# uC.net
KiCad netlist of a schematic drawn in Altium Designer
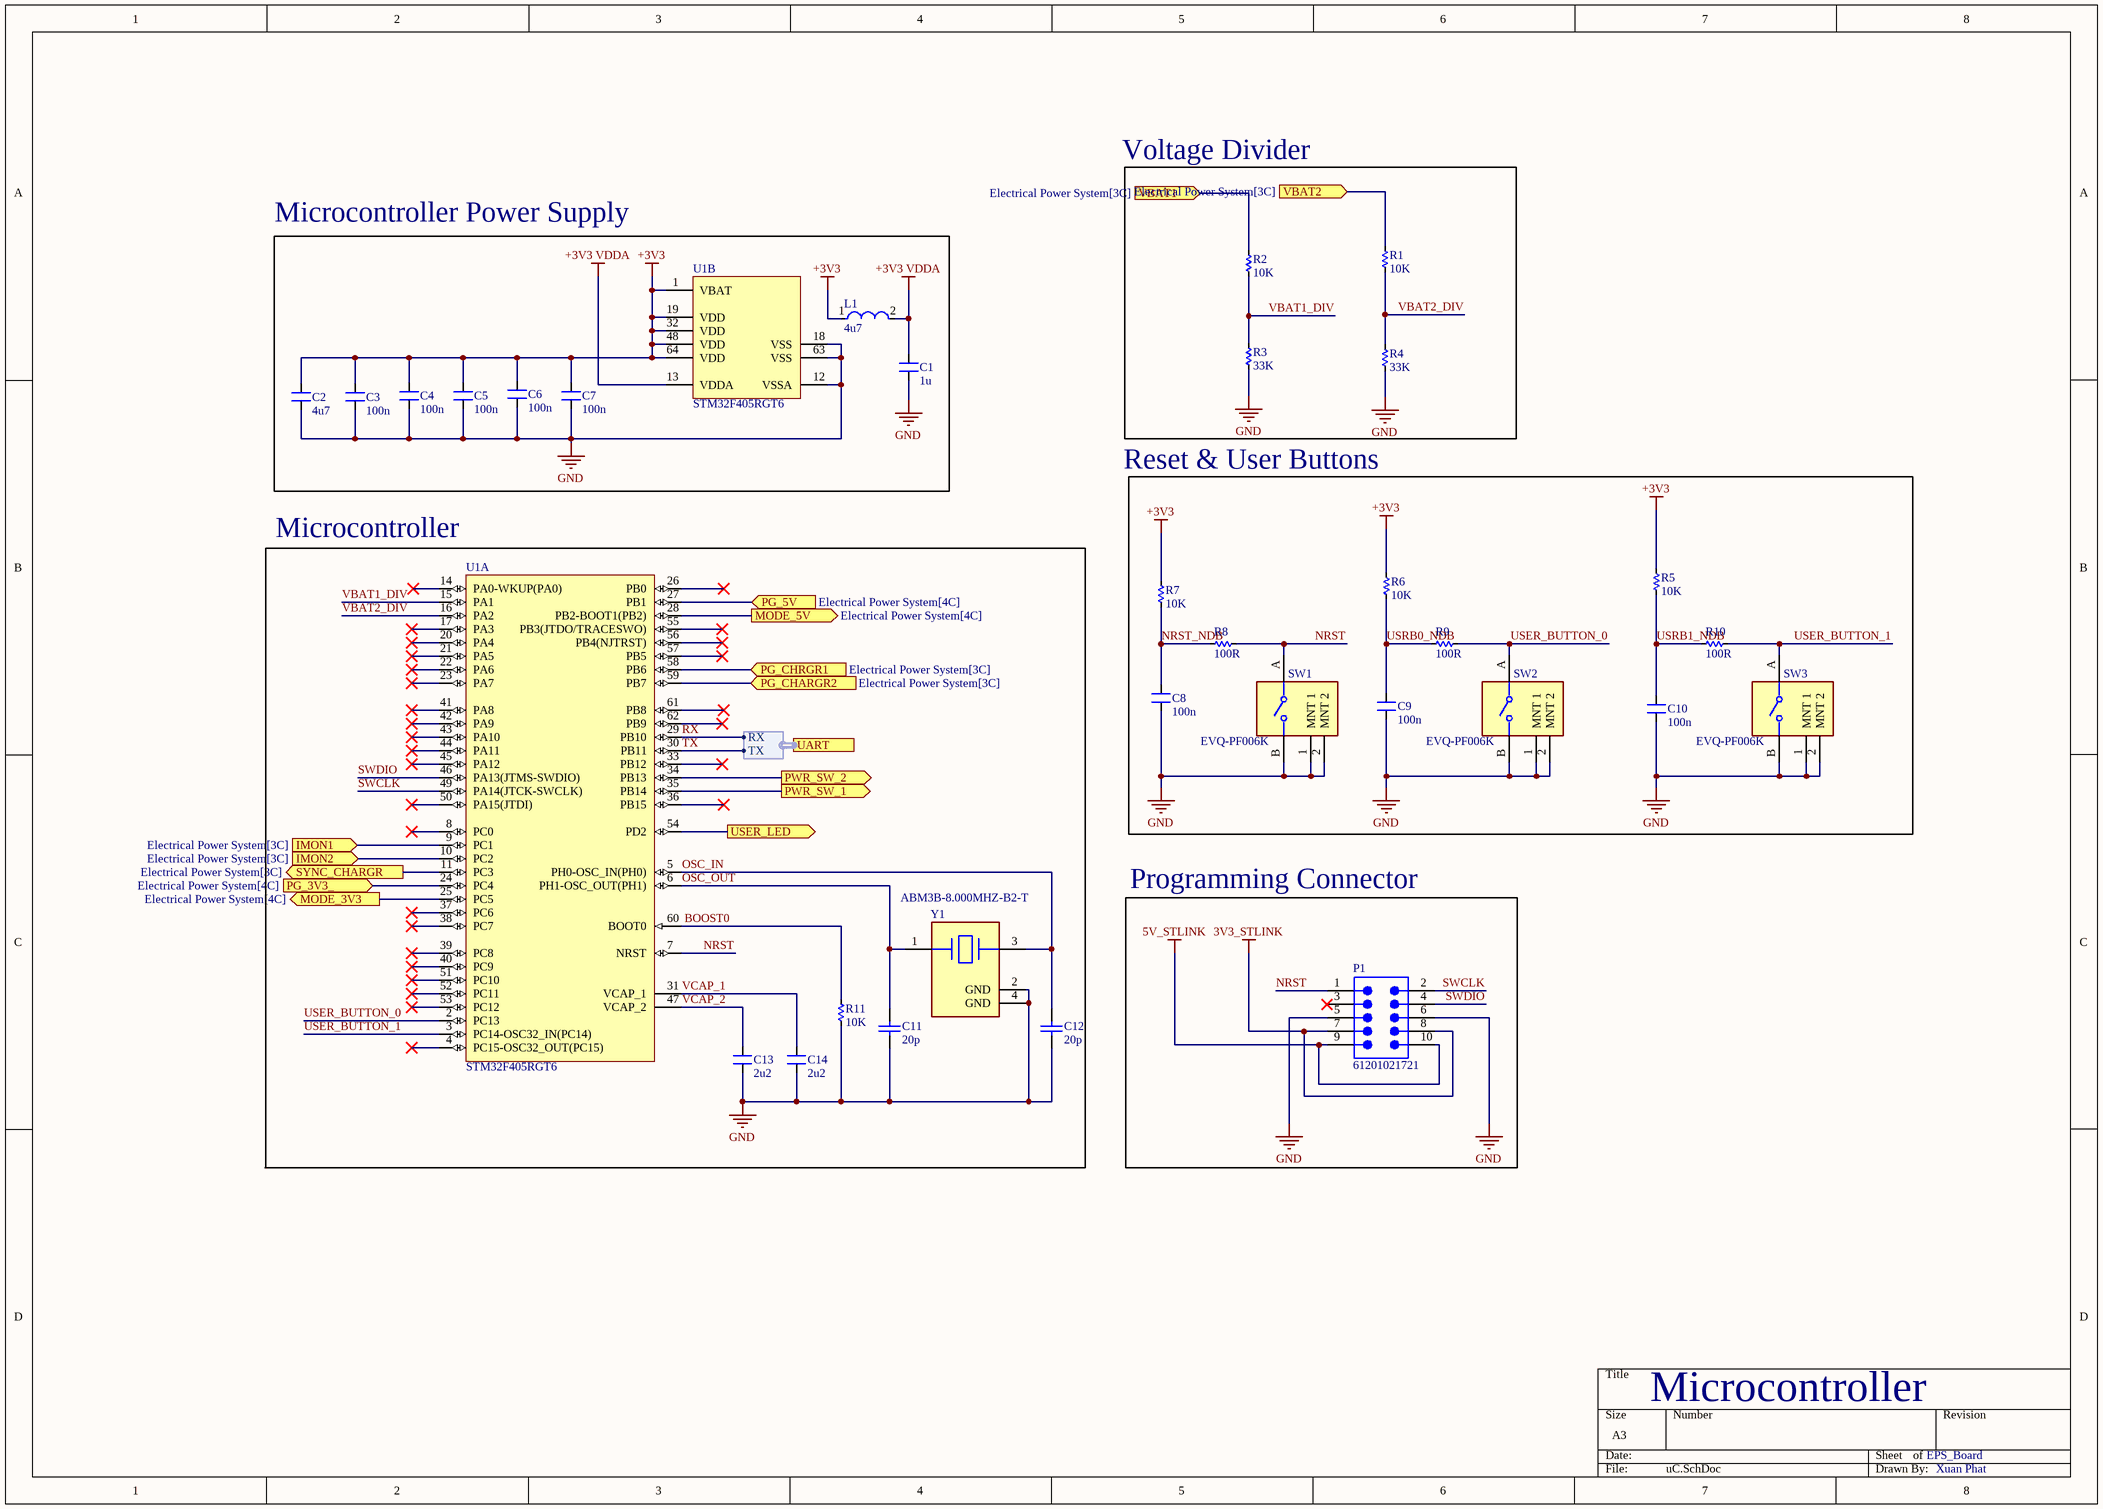
[diagram p0: uC.SchDoc]

(export (version "E")
  (design (tool "Eeschema 10.0.6"))
  (components
    (comp (ref "C1")
      (value "1u")
      (footprint "CN-SMD-0603")
      (libsource (lib "Sang_library") (part "Capacitors"))
    )
    (comp (ref "C2")
      (value "4u7")
      (footprint "CN-SMD-0603")
      (libsource (lib "Sang_library") (part "Capacitors"))
    )
    (comp (ref "C3")
      (value "100n")
      (footprint "CN-SMD-0603")
      (libsource (lib "Sang_library") (part "Capacitors"))
    )
    (comp (ref "C4")
      (value "100n")
      (footprint "CN-SMD-0603")
      (libsource (lib "Sang_library") (part "Capacitors"))
    )
    (comp (ref "C5")
      (value "100n")
      (footprint "CN-SMD-0603")
      (libsource (lib "Sang_library") (part "Capacitors"))
    )
    (comp (ref "C6")
      (value "100n")
      (footprint "CN-SMD-0603")
      (libsource (lib "Sang_library") (part "Capacitors"))
    )
    (comp (ref "C7")
      (value "100n")
      (footprint "CN-SMD-0603")
      (libsource (lib "Sang_library") (part "Capacitors"))
    )
    (comp (ref "C8")
      (value "100n")
      (footprint "CN-SMD-0603")
      (libsource (lib "Sang_library") (part "Capacitors"))
    )
    (comp (ref "C9")
      (value "100n")
      (footprint "CN-SMD-0603")
      (libsource (lib "Sang_library") (part "Capacitors"))
    )
    (comp (ref "C10")
      (value "100n")
      (footprint "CN-SMD-0603")
      (libsource (lib "Sang_library") (part "Capacitors"))
    )
    (comp (ref "C11")
      (value "20p")
      (footprint "CAPC1608X90X30LL10T20")
      (description "Chip Capacitor, 20 pF, +/- 5%, 50 V, -55 to 85 degC, 0603 (1608 Metric), RoHS, Tape and Reel")
      (fields (field (name "MANUFACTURER") "Samsung Electro-Mechanics"))
      (libsource (lib "Altium Content Vault") (part "CAP-NP-2"))
    )
    (comp (ref "C12")
      (value "20p")
      (footprint "CAPC1608X90X30LL10T20")
      (description "Chip Capacitor, 20 pF, +/- 5%, 50 V, -55 to 85 degC, 0603 (1608 Metric), RoHS, Tape and Reel")
      (fields (field (name "MANUFACTURER") "Samsung Electro-Mechanics"))
      (libsource (lib "Altium Content Vault") (part "CAP-NP-2"))
    )
    (comp (ref "C13")
      (value "2u2")
      (footprint "CN-SMD-0603")
      (libsource (lib "Sang_library") (part "Capacitors"))
    )
    (comp (ref "C14")
      (value "2u2")
      (footprint "CN-SMD-0603")
      (libsource (lib "Sang_library") (part "Capacitors"))
    )
    (comp (ref "L1")
      (value "4u7")
      (footprint "FP-LQM2HPN_G0-IPC_A")
      (description "Multilayer Type Inductor for Power Lines, 1008 (2520), 4.7μH, 20%, 0.138Ω, 1.1A")
      (fields (field (name "TOLERANCE") "20%"))
      (libsource (lib "Altium Content Vault") (part "725321dda6339637d4d059423bc1c3c"))
    )
    (comp (ref "P1")
      (value "61201021721")
      (footprint "61201021721")
      (libsource (lib "Altium Content Vault") (part "Header_Male_2R_10P"))
    )
    (comp (ref "R1")
      (value "10K")
      (footprint "RES-SMD-0805")
      (description "SMD")
      (fields
        (field (name "MANUFACTURER") "Generic Components")
        (field (name "PUBLISHER") "Altium Hobart Technology Centre")
      )
      (libsource (lib "Sang_library") (part "Res SMD"))
    )
    (comp (ref "R2")
      (value "10K")
      (footprint "RES-SMD-0805")
      (description "SMD")
      (fields
        (field (name "MANUFACTURER") "Generic Components")
        (field (name "PUBLISHER") "Altium Hobart Technology Centre")
      )
      (libsource (lib "Sang_library") (part "Res SMD"))
    )
    (comp (ref "R3")
      (value "33K")
      (footprint "RES-SMD-0805")
      (description "SMD")
      (fields
        (field (name "MANUFACTURER") "Generic Components")
        (field (name "PUBLISHER") "Altium Hobart Technology Centre")
      )
      (libsource (lib "Sang_library") (part "Res SMD"))
    )
    (comp (ref "R4")
      (value "33K")
      (footprint "RES-SMD-0805")
      (description "SMD")
      (fields
        (field (name "MANUFACTURER") "Generic Components")
        (field (name "PUBLISHER") "Altium Hobart Technology Centre")
      )
      (libsource (lib "Sang_library") (part "Res SMD"))
    )
    (comp (ref "R5")
      (value "10K")
      (footprint "RES-SMD-0805")
      (description "SMD")
      (fields
        (field (name "MANUFACTURER") "Generic Components")
        (field (name "PUBLISHER") "Altium Hobart Technology Centre")
      )
      (libsource (lib "Sang_library") (part "Res SMD"))
    )
    (comp (ref "R6")
      (value "10K")
      (footprint "RES-SMD-0805")
      (description "SMD")
      (fields
        (field (name "MANUFACTURER") "Generic Components")
        (field (name "PUBLISHER") "Altium Hobart Technology Centre")
      )
      (libsource (lib "Sang_library") (part "Res SMD"))
    )
    (comp (ref "R7")
      (value "10K")
      (footprint "RES-SMD-0805")
      (description "SMD")
      (fields
        (field (name "MANUFACTURER") "Generic Components")
        (field (name "PUBLISHER") "Altium Hobart Technology Centre")
      )
      (libsource (lib "Sang_library") (part "Res SMD"))
    )
    (comp (ref "R8")
      (value "100R")
      (footprint "RES-SMD-0805")
      (description "SMD")
      (fields
        (field (name "MANUFACTURER") "Generic Components")
        (field (name "PUBLISHER") "Altium Hobart Technology Centre")
      )
      (libsource (lib "Sang_library") (part "Res SMD"))
    )
    (comp (ref "R9")
      (value "100R")
      (footprint "RES-SMD-0805")
      (description "SMD")
      (fields
        (field (name "MANUFACTURER") "Generic Components")
        (field (name "PUBLISHER") "Altium Hobart Technology Centre")
      )
      (libsource (lib "Sang_library") (part "Res SMD"))
    )
    (comp (ref "R10")
      (value "100R")
      (footprint "RES-SMD-0805")
      (description "SMD")
      (fields
        (field (name "MANUFACTURER") "Generic Components")
        (field (name "PUBLISHER") "Altium Hobart Technology Centre")
      )
      (libsource (lib "Sang_library") (part "Res SMD"))
    )
    (comp (ref "R11")
      (value "10K")
      (footprint "RES-SMD-0805")
      (description "SMD")
      (fields
        (field (name "MANUFACTURER") "Generic Components")
        (field (name "PUBLISHER") "Altium Hobart Technology Centre")
      )
      (libsource (lib "Sang_library") (part "Res SMD"))
    )
    (comp (ref "SW1")
      (value "EVQ-PF006K")
      (footprint "FP-EVQ-PF006K-MFG")
      (description "EVQ-PF006K Switch Tactile N.O. SPST Round Button PC Pins 0.02A 15VDC 1N Thru-Hole Bulk")
      (libsource (lib "Altium Content Vault") (part "05786d9cdc9c8df32985042e91d1e9f"))
    )
    (comp (ref "SW2")
      (value "EVQ-PF006K")
      (footprint "FP-EVQ-PF006K-MFG")
      (description "EVQ-PF006K Switch Tactile N.O. SPST Round Button PC Pins 0.02A 15VDC 1N Thru-Hole Bulk")
      (libsource (lib "Altium Content Vault") (part "05786d9cdc9c8df32985042e91d1e9f"))
    )
    (comp (ref "SW3")
      (value "EVQ-PF006K")
      (footprint "FP-EVQ-PF006K-MFG")
      (description "EVQ-PF006K Switch Tactile N.O. SPST Round Button PC Pins 0.02A 15VDC 1N Thru-Hole Bulk")
      (libsource (lib "Altium Content Vault") (part "05786d9cdc9c8df32985042e91d1e9f"))
    )
    (comp (ref "U1")
      (value "STM32F405RGT6")
      (footprint "STM-LQFP64_M")
      (fields (field (name "MANUFACTURER") "STMicroelectronics"))
      (libsource (lib "Altium Content Vault") (part "MC-ARM-STM32F4X5-SQ64"))
    )
    (comp (ref "Y1")
      (value "ABM3B-8.000MHZ-B2-T")
      (footprint "FP-ABM3B-MFG")
      (description "Crystal 8MHz ±20ppm 18pF SMD-4 5mm x 3.2mm")
      (fields (field (name "TOLERANCE") "20ppm"))
      (libsource (lib "Altium Content Vault") (part "48e526d86b7f2615d98721063c72f49"))
    )
  )
  (nets
    (net (code "2") (name "+3V3") (class "Default")
      (node (ref "C2") (pin "2") (pinfunction "2_2") (pintype "passive"))
      (node (ref "C3") (pin "2") (pinfunction "2_2") (pintype "passive"))
      (node (ref "C4") (pin "2") (pinfunction "2_2") (pintype "passive"))
      (node (ref "C5") (pin "2") (pinfunction "2_2") (pintype "passive"))
      (node (ref "C6") (pin "2") (pinfunction "2_2") (pintype "passive"))
      (node (ref "C7") (pin "2") (pinfunction "2_2") (pintype "passive"))
      (node (ref "L1") (pin "1") (pinfunction "1_1") (pintype "passive"))
      (node (ref "R5") (pin "1") (pinfunction "1_1") (pintype "passive"))
      (node (ref "R6") (pin "1") (pinfunction "1_1") (pintype "passive"))
      (node (ref "R7") (pin "1") (pinfunction "1_1") (pintype "passive"))
      (node (ref "U1") (pin "1") (pinfunction "VBAT_1") (pintype "power_in"))
      (node (ref "U1") (pin "19") (pinfunction "VDD_19") (pintype "power_in"))
      (node (ref "U1") (pin "32") (pinfunction "VDD_32") (pintype "power_in"))
      (node (ref "U1") (pin "48") (pinfunction "VDD_48") (pintype "power_in"))
      (node (ref "U1") (pin "64") (pinfunction "VDD_64") (pintype "power_in"))
    )
    (net (code "3") (name "+3V3 VDDA") (class "Default")
      (node (ref "C1") (pin "2") (pinfunction "2_2") (pintype "passive"))
      (node (ref "L1") (pin "2") (pinfunction "2_2") (pintype "passive"))
      (node (ref "U1") (pin "13") (pinfunction "VDDA_13") (pintype "power_in"))
    )
    (net (code "4") (name "/BOOST0") (class "Default")
      (node (ref "R11") (pin "1") (pinfunction "1_1") (pintype "passive"))
      (node (ref "U1") (pin "60") (pinfunction "BOOT0_60") (pintype "input"))
    )
    (net (code "5") (name "/IMON1") (class "Default")
      (node (ref "U1") (pin "9") (pinfunction "PC1_9") (pintype "bidirectional"))
    )
    (net (code "6") (name "/IMON2") (class "Default")
      (node (ref "U1") (pin "10") (pinfunction "PC2_10") (pintype "bidirectional"))
    )
    (net (code "7") (name "/MODE_3V3") (class "Default")
      (node (ref "U1") (pin "25") (pinfunction "PC5_25") (pintype "bidirectional"))
    )
    (net (code "8") (name "/MODE_5V") (class "Default")
      (node (ref "U1") (pin "28") (pinfunction "PB2-BOOT1(PB2)_28") (pintype "bidirectional"))
    )
    (net (code "9") (name "/NRST") (class "Default")
      (node (ref "P1") (pin "1") (pinfunction "1_1") (pintype "passive"))
      (node (ref "R8") (pin "2") (pinfunction "2_2") (pintype "passive"))
      (node (ref "SW1") (pin "A") (pinfunction "A_A") (pintype "passive"))
      (node (ref "U1") (pin "7") (pinfunction "NRST_7") (pintype "bidirectional"))
    )
    (net (code "10") (name "/NRST_NDB") (class "Default")
      (node (ref "C8") (pin "2") (pinfunction "2_2") (pintype "passive"))
      (node (ref "R7") (pin "2") (pinfunction "2_2") (pintype "passive"))
      (node (ref "R8") (pin "1") (pinfunction "1_1") (pintype "passive"))
    )
    (net (code "11") (name "/OSC_IN") (class "Default")
      (node (ref "C12") (pin "2") (pinfunction "2_2") (pintype "passive"))
      (node (ref "U1") (pin "5") (pinfunction "PH0-OSC_IN(PH0)_5") (pintype "bidirectional"))
      (node (ref "Y1") (pin "3") (pinfunction "3_3") (pintype "passive"))
    )
    (net (code "12") (name "/OSC_OUT") (class "Default")
      (node (ref "C11") (pin "2") (pinfunction "2_2") (pintype "passive"))
      (node (ref "U1") (pin "6") (pinfunction "PH1-OSC_OUT(PH1)_6") (pintype "bidirectional"))
      (node (ref "Y1") (pin "1") (pinfunction "1_1") (pintype "passive"))
    )
    (net (code "13") (name "/PG_3V3_") (class "Default")
      (node (ref "U1") (pin "24") (pinfunction "PC4_24") (pintype "bidirectional"))
    )
    (net (code "14") (name "/PG_5V") (class "Default")
      (node (ref "U1") (pin "27") (pinfunction "PB1_27") (pintype "bidirectional"))
    )
    (net (code "15") (name "/PG_CHARGR2") (class "Default")
      (node (ref "U1") (pin "59") (pinfunction "PB7_59") (pintype "bidirectional"))
    )
    (net (code "16") (name "/PG_CHRGR1") (class "Default")
      (node (ref "U1") (pin "58") (pinfunction "PB6_58") (pintype "bidirectional"))
    )
    (net (code "17") (name "/PWR_SW_1") (class "Default")
      (node (ref "U1") (pin "35") (pinfunction "PB14_35") (pintype "bidirectional"))
    )
    (net (code "18") (name "/PWR_SW_2") (class "Default")
      (node (ref "U1") (pin "34") (pinfunction "PB13_34") (pintype "bidirectional"))
    )
    (net (code "19") (name "/RX") (class "Default")
      (node (ref "U1") (pin "29") (pinfunction "PB10_29") (pintype "bidirectional"))
    )
    (net (code "20") (name "/SWCLK") (class "Default")
      (node (ref "P1") (pin "2") (pinfunction "2_2") (pintype "passive"))
      (node (ref "U1") (pin "49") (pinfunction "PA14(JTCK-SWCLK)_49") (pintype "bidirectional"))
    )
    (net (code "21") (name "/SWDIO") (class "Default")
      (node (ref "P1") (pin "4") (pinfunction "4_4") (pintype "passive"))
      (node (ref "U1") (pin "46") (pinfunction "PA13(JTMS-SWDIO)_46") (pintype "bidirectional"))
    )
    (net (code "22") (name "/SYNC_CHARGR") (class "Default")
      (node (ref "U1") (pin "11") (pinfunction "PC3_11") (pintype "bidirectional"))
    )
    (net (code "23") (name "/TX") (class "Default")
      (node (ref "U1") (pin "30") (pinfunction "PB11_30") (pintype "bidirectional"))
    )
    (net (code "24") (name "/USER_BUTTON_0") (class "Default")
      (node (ref "R9") (pin "2") (pinfunction "2_2") (pintype "passive"))
      (node (ref "SW2") (pin "A") (pinfunction "A_A") (pintype "passive"))
      (node (ref "U1") (pin "2") (pinfunction "PC13_2") (pintype "bidirectional"))
    )
    (net (code "25") (name "/USER_BUTTON_1") (class "Default")
      (node (ref "R10") (pin "2") (pinfunction "2_2") (pintype "passive"))
      (node (ref "SW3") (pin "A") (pinfunction "A_A") (pintype "passive"))
      (node (ref "U1") (pin "3") (pinfunction "PC14-OSC32_IN(PC14)_3") (pintype "bidirectional"))
    )
    (net (code "26") (name "/USER_LED") (class "Default")
      (node (ref "U1") (pin "54") (pinfunction "PD2_54") (pintype "bidirectional"))
    )
    (net (code "27") (name "/USRB0_NDB") (class "Default")
      (node (ref "C9") (pin "2") (pinfunction "2_2") (pintype "passive"))
      (node (ref "R6") (pin "2") (pinfunction "2_2") (pintype "passive"))
      (node (ref "R9") (pin "1") (pinfunction "1_1") (pintype "passive"))
    )
    (net (code "28") (name "/USRB1_NDB") (class "Default")
      (node (ref "C10") (pin "2") (pinfunction "2_2") (pintype "passive"))
      (node (ref "R10") (pin "1") (pinfunction "1_1") (pintype "passive"))
      (node (ref "R5") (pin "2") (pinfunction "2_2") (pintype "passive"))
    )
    (net (code "29") (name "/VBAT1") (class "Default")
      (node (ref "R2") (pin "1") (pinfunction "1_1") (pintype "passive"))
    )
    (net (code "30") (name "/VBAT1_DIV") (class "Default")
      (node (ref "R2") (pin "2") (pinfunction "2_2") (pintype "passive"))
      (node (ref "R3") (pin "1") (pinfunction "1_1") (pintype "passive"))
      (node (ref "U1") (pin "15") (pinfunction "PA1_15") (pintype "bidirectional"))
    )
    (net (code "31") (name "/VBAT2") (class "Default")
      (node (ref "R1") (pin "1") (pinfunction "1_1") (pintype "passive"))
    )
    (net (code "32") (name "/VBAT2_DIV") (class "Default")
      (node (ref "R1") (pin "2") (pinfunction "2_2") (pintype "passive"))
      (node (ref "R4") (pin "1") (pinfunction "1_1") (pintype "passive"))
      (node (ref "U1") (pin "16") (pinfunction "PA2_16") (pintype "bidirectional"))
    )
    (net (code "33") (name "/VCAP_1") (class "Default")
      (node (ref "C14") (pin "2") (pinfunction "2_2") (pintype "passive"))
      (node (ref "U1") (pin "31") (pinfunction "VCAP_1_31") (pintype "power_in"))
    )
    (net (code "34") (name "/VCAP_2") (class "Default")
      (node (ref "C13") (pin "2") (pinfunction "2_2") (pintype "passive"))
      (node (ref "U1") (pin "47") (pinfunction "VCAP_2_47") (pintype "power_in"))
    )
    (net (code "36") (name "3V3_STLINK") (class "Default")
      (node (ref "P1") (pin "7") (pinfunction "7_7") (pintype "passive"))
      (node (ref "P1") (pin "8") (pinfunction "8_8") (pintype "passive"))
    )
    (net (code "37") (name "5V_STLINK") (class "Default")
      (node (ref "P1") (pin "10") (pinfunction "10_10") (pintype "passive"))
      (node (ref "P1") (pin "9") (pinfunction "9_9") (pintype "passive"))
    )
    (net (code "38") (name "GND") (class "Default")
      (node (ref "C1") (pin "1") (pinfunction "1_1") (pintype "passive"))
      (node (ref "C10") (pin "1") (pinfunction "1_1") (pintype "passive"))
      (node (ref "C11") (pin "1") (pinfunction "1_1") (pintype "passive"))
      (node (ref "C12") (pin "1") (pinfunction "1_1") (pintype "passive"))
      (node (ref "C13") (pin "1") (pinfunction "1_1") (pintype "passive"))
      (node (ref "C14") (pin "1") (pinfunction "1_1") (pintype "passive"))
      (node (ref "C2") (pin "1") (pinfunction "1_1") (pintype "passive"))
      (node (ref "C3") (pin "1") (pinfunction "1_1") (pintype "passive"))
      (node (ref "C4") (pin "1") (pinfunction "1_1") (pintype "passive"))
      (node (ref "C5") (pin "1") (pinfunction "1_1") (pintype "passive"))
      (node (ref "C6") (pin "1") (pinfunction "1_1") (pintype "passive"))
      (node (ref "C7") (pin "1") (pinfunction "1_1") (pintype "passive"))
      (node (ref "C8") (pin "1") (pinfunction "1_1") (pintype "passive"))
      (node (ref "C9") (pin "1") (pinfunction "1_1") (pintype "passive"))
      (node (ref "P1") (pin "5") (pinfunction "5_5") (pintype "passive"))
      (node (ref "P1") (pin "6") (pinfunction "6_6") (pintype "passive"))
      (node (ref "R11") (pin "2") (pinfunction "2_2") (pintype "passive"))
      (node (ref "R3") (pin "2") (pinfunction "2_2") (pintype "passive"))
      (node (ref "R4") (pin "2") (pinfunction "2_2") (pintype "passive"))
      (node (ref "SW1") (pin "1") (pinfunction "MNT_1_1") (pintype "passive"))
      (node (ref "SW1") (pin "2") (pinfunction "MNT_2_2") (pintype "passive"))
      (node (ref "SW1") (pin "B") (pinfunction "B_B") (pintype "passive"))
      (node (ref "SW2") (pin "1") (pinfunction "MNT_1_1") (pintype "passive"))
      (node (ref "SW2") (pin "2") (pinfunction "MNT_2_2") (pintype "passive"))
      (node (ref "SW2") (pin "B") (pinfunction "B_B") (pintype "passive"))
      (node (ref "SW3") (pin "1") (pinfunction "MNT_1_1") (pintype "passive"))
      (node (ref "SW3") (pin "2") (pinfunction "MNT_2_2") (pintype "passive"))
      (node (ref "SW3") (pin "B") (pinfunction "B_B") (pintype "passive"))
      (node (ref "U1") (pin "12") (pinfunction "VSSA_12") (pintype "power_in"))
      (node (ref "U1") (pin "18") (pinfunction "VSS_18") (pintype "power_in"))
      (node (ref "U1") (pin "63") (pinfunction "VSS_63") (pintype "power_in"))
      (node (ref "Y1") (pin "2") (pinfunction "GND_2") (pintype "power_in"))
      (node (ref "Y1") (pin "4") (pinfunction "GND_4") (pintype "power_in"))
    )
    (net (code "39") (name "unconnected-(P1-Pad3)") (class "Default")
      (node (ref "P1") (pin "3") (pinfunction "3_3") (pintype "passive+no_connect"))
    )
    (net (code "40") (name "unconnected-(U1A-PA0-WKUP(PA0)-Pad14)") (class "Default")
      (node (ref "U1") (pin "14") (pinfunction "PA0-WKUP(PA0)_14") (pintype "bidirectional+no_connect"))
    )
    (net (code "41") (name "unconnected-(U1A-PA3-Pad17)") (class "Default")
      (node (ref "U1") (pin "17") (pinfunction "PA3_17") (pintype "bidirectional+no_connect"))
    )
    (net (code "42") (name "unconnected-(U1A-PA4-Pad20)") (class "Default")
      (node (ref "U1") (pin "20") (pinfunction "PA4_20") (pintype "bidirectional+no_connect"))
    )
    (net (code "43") (name "unconnected-(U1A-PA5-Pad21)") (class "Default")
      (node (ref "U1") (pin "21") (pinfunction "PA5_21") (pintype "bidirectional+no_connect"))
    )
    (net (code "44") (name "unconnected-(U1A-PA6-Pad22)") (class "Default")
      (node (ref "U1") (pin "22") (pinfunction "PA6_22") (pintype "bidirectional+no_connect"))
    )
    (net (code "45") (name "unconnected-(U1A-PA7-Pad23)") (class "Default")
      (node (ref "U1") (pin "23") (pinfunction "PA7_23") (pintype "bidirectional+no_connect"))
    )
    (net (code "46") (name "unconnected-(U1A-PA8-Pad41)") (class "Default")
      (node (ref "U1") (pin "41") (pinfunction "PA8_41") (pintype "bidirectional+no_connect"))
    )
    (net (code "47") (name "unconnected-(U1A-PA9-Pad42)") (class "Default")
      (node (ref "U1") (pin "42") (pinfunction "PA9_42") (pintype "bidirectional+no_connect"))
    )
    (net (code "48") (name "unconnected-(U1A-PA10-Pad43)") (class "Default")
      (node (ref "U1") (pin "43") (pinfunction "PA10_43") (pintype "bidirectional+no_connect"))
    )
    (net (code "49") (name "unconnected-(U1A-PA11-Pad44)") (class "Default")
      (node (ref "U1") (pin "44") (pinfunction "PA11_44") (pintype "bidirectional+no_connect"))
    )
    (net (code "50") (name "unconnected-(U1A-PA12-Pad45)") (class "Default")
      (node (ref "U1") (pin "45") (pinfunction "PA12_45") (pintype "bidirectional+no_connect"))
    )
    (net (code "51") (name "unconnected-(U1A-PA15(JTDI)-Pad50)") (class "Default")
      (node (ref "U1") (pin "50") (pinfunction "PA15(JTDI)_50") (pintype "bidirectional+no_connect"))
    )
    (net (code "52") (name "unconnected-(U1A-PB0-Pad26)") (class "Default")
      (node (ref "U1") (pin "26") (pinfunction "PB0_26") (pintype "bidirectional+no_connect"))
    )
    (net (code "53") (name "unconnected-(U1A-PB3(JTDO{slash}TRACESWO)-Pad55)") (class "Default")
      (node (ref "U1") (pin "55") (pinfunction "PB3(JTDO/TRACESWO)_55") (pintype "bidirectional+no_connect"))
    )
    (net (code "54") (name "unconnected-(U1A-PB4(NJTRST)-Pad56)") (class "Default")
      (node (ref "U1") (pin "56") (pinfunction "PB4(NJTRST)_56") (pintype "bidirectional+no_connect"))
    )
    (net (code "55") (name "unconnected-(U1A-PB5-Pad57)") (class "Default")
      (node (ref "U1") (pin "57") (pinfunction "PB5_57") (pintype "bidirectional+no_connect"))
    )
    (net (code "56") (name "unconnected-(U1A-PB8-Pad61)") (class "Default")
      (node (ref "U1") (pin "61") (pinfunction "PB8_61") (pintype "bidirectional+no_connect"))
    )
    (net (code "57") (name "unconnected-(U1A-PB9-Pad62)") (class "Default")
      (node (ref "U1") (pin "62") (pinfunction "PB9_62") (pintype "bidirectional+no_connect"))
    )
    (net (code "58") (name "unconnected-(U1A-PB12-Pad33)") (class "Default")
      (node (ref "U1") (pin "33") (pinfunction "PB12_33") (pintype "bidirectional+no_connect"))
    )
    (net (code "59") (name "unconnected-(U1A-PB15-Pad36)") (class "Default")
      (node (ref "U1") (pin "36") (pinfunction "PB15_36") (pintype "bidirectional+no_connect"))
    )
    (net (code "60") (name "unconnected-(U1A-PC0-Pad8)") (class "Default")
      (node (ref "U1") (pin "8") (pinfunction "PC0_8") (pintype "bidirectional+no_connect"))
    )
    (net (code "61") (name "unconnected-(U1A-PC6-Pad37)") (class "Default")
      (node (ref "U1") (pin "37") (pinfunction "PC6_37") (pintype "bidirectional+no_connect"))
    )
    (net (code "62") (name "unconnected-(U1A-PC7-Pad38)") (class "Default")
      (node (ref "U1") (pin "38") (pinfunction "PC7_38") (pintype "bidirectional+no_connect"))
    )
    (net (code "63") (name "unconnected-(U1A-PC8-Pad39)") (class "Default")
      (node (ref "U1") (pin "39") (pinfunction "PC8_39") (pintype "bidirectional+no_connect"))
    )
    (net (code "64") (name "unconnected-(U1A-PC9-Pad40)") (class "Default")
      (node (ref "U1") (pin "40") (pinfunction "PC9_40") (pintype "bidirectional+no_connect"))
    )
    (net (code "65") (name "unconnected-(U1A-PC10-Pad51)") (class "Default")
      (node (ref "U1") (pin "51") (pinfunction "PC10_51") (pintype "bidirectional+no_connect"))
    )
    (net (code "66") (name "unconnected-(U1A-PC11-Pad52)") (class "Default")
      (node (ref "U1") (pin "52") (pinfunction "PC11_52") (pintype "bidirectional+no_connect"))
    )
    (net (code "67") (name "unconnected-(U1A-PC12-Pad53)") (class "Default")
      (node (ref "U1") (pin "53") (pinfunction "PC12_53") (pintype "bidirectional+no_connect"))
    )
    (net (code "68") (name "unconnected-(U1A-PC15-OSC32_OUT(PC15)-Pad4)") (class "Default")
      (node (ref "U1") (pin "4") (pinfunction "PC15-OSC32_OUT(PC15)_4") (pintype "bidirectional+no_connect"))
    )
  )
)
